# PROB_S7CAS_FPGA_2.net
KiCad netlist of a schematic drawn in Altium Designer
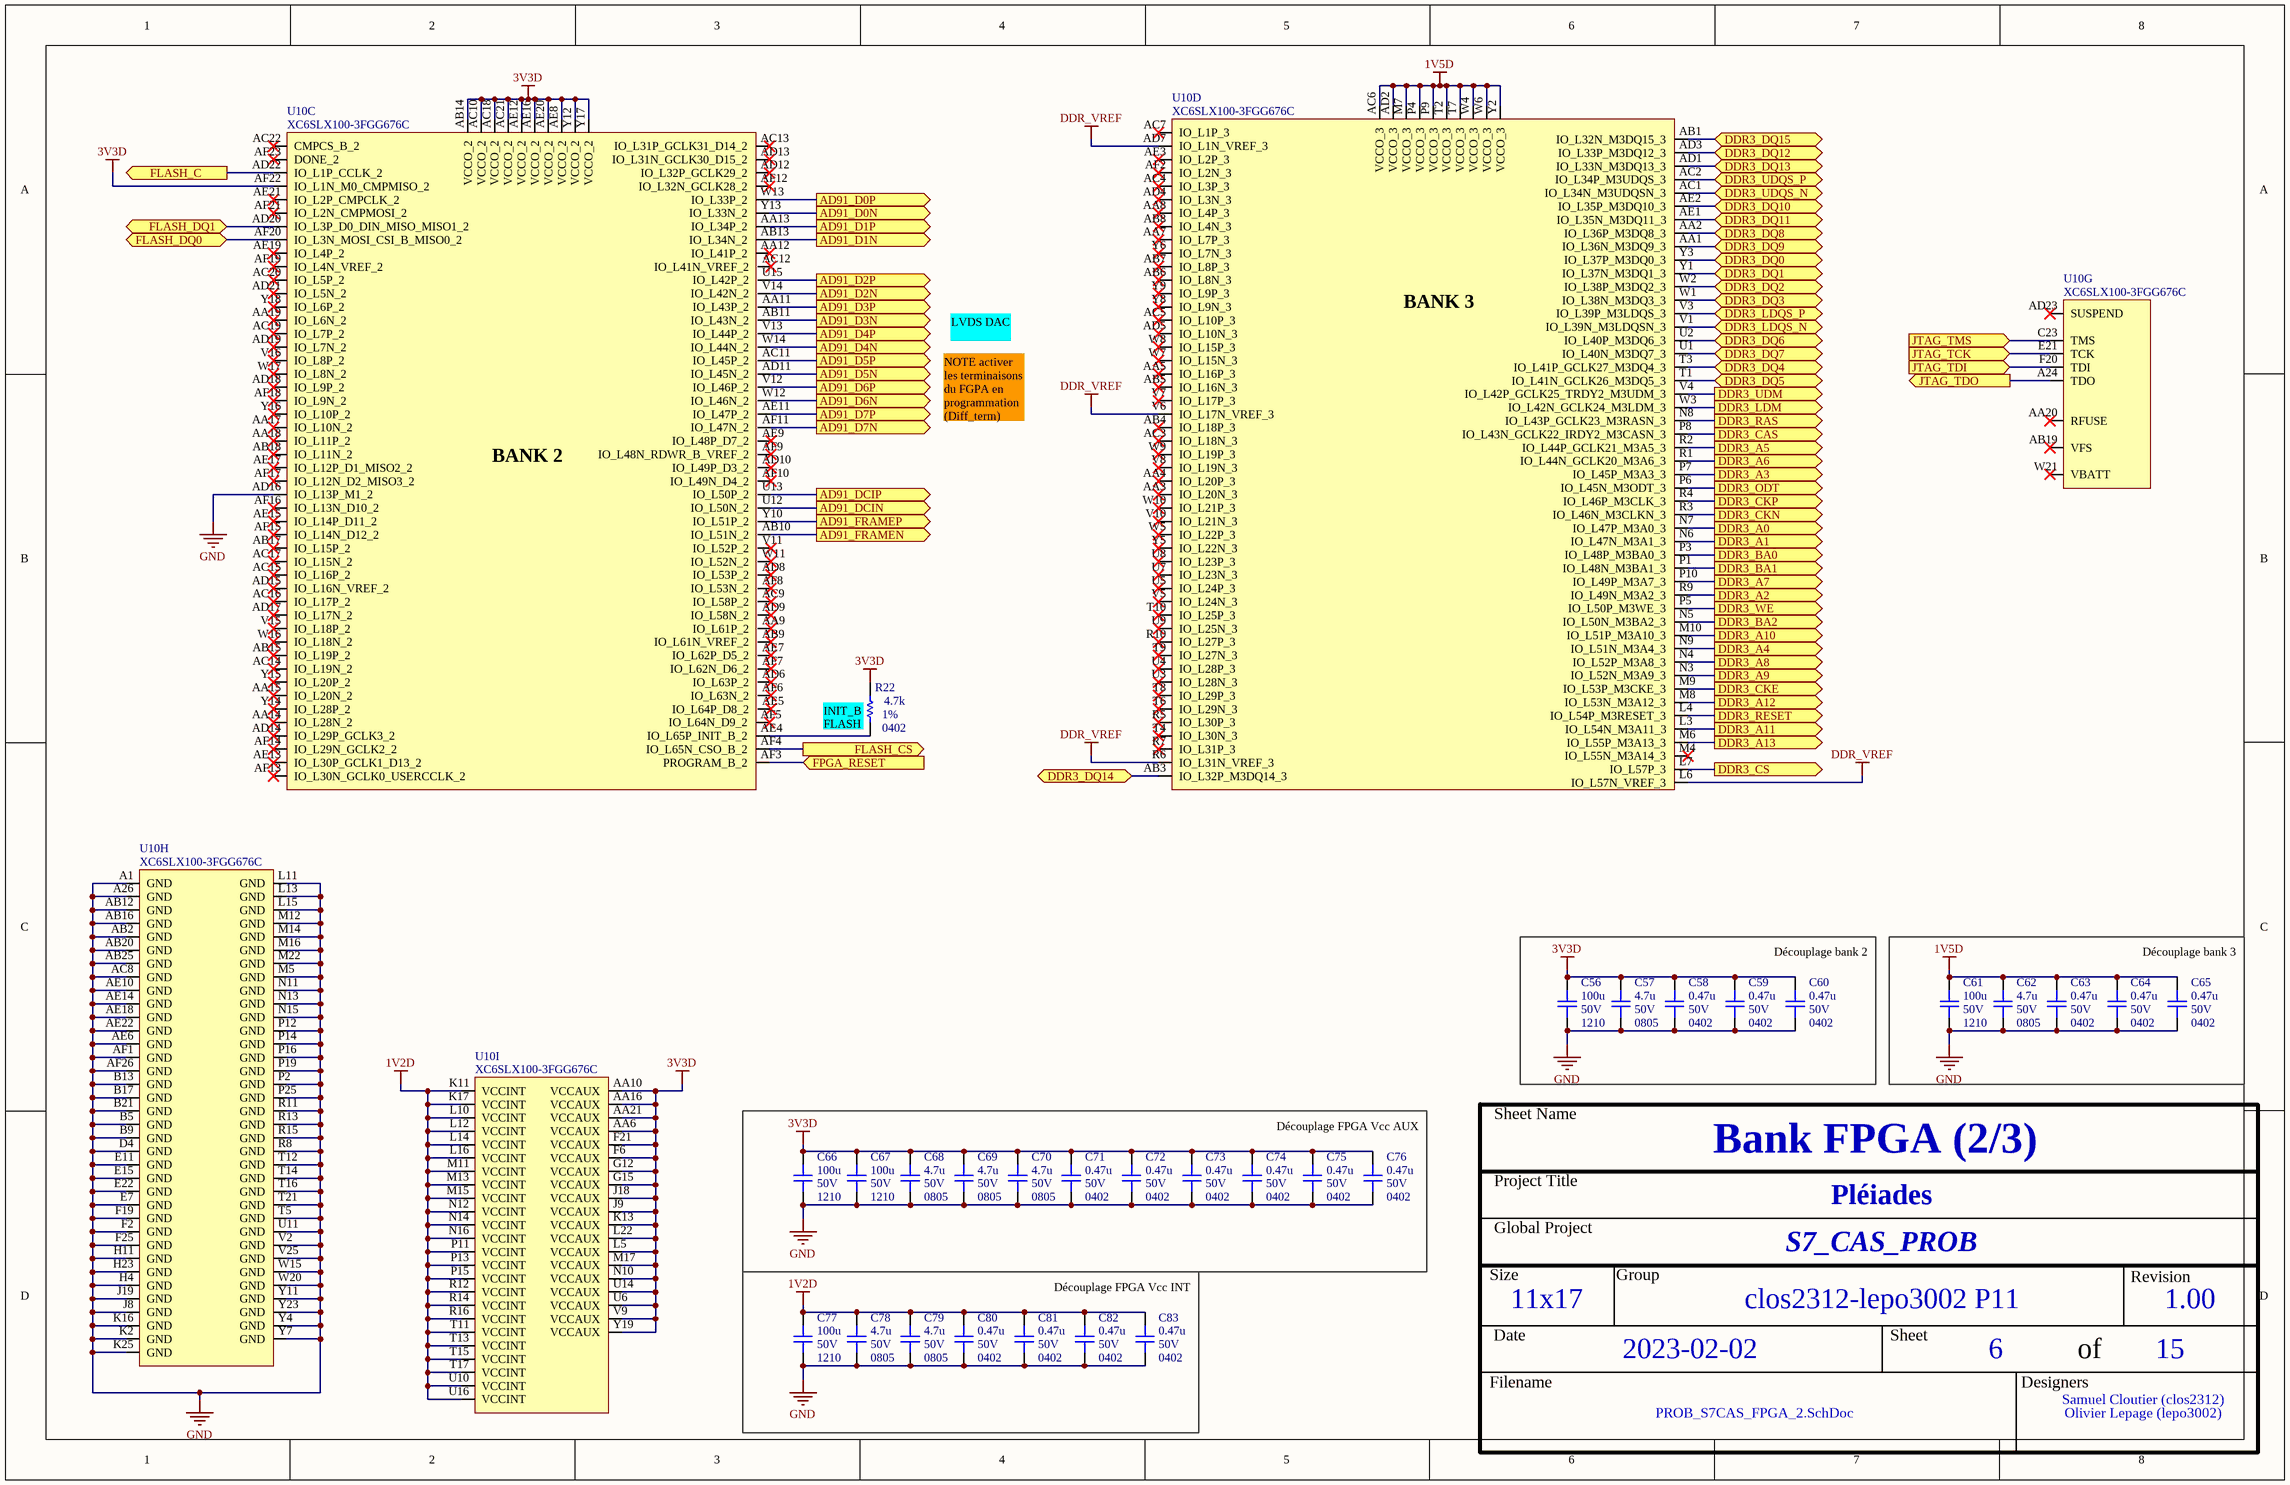
[diagram p0: PROB_S7CAS_FPGA_2.SchDoc]

(export (version "E")
  (design (tool "Eeschema 10.0.6"))
  (components
    (comp (ref "C56")
      (value "100u")
      (footprint "CAP_1210")
      (description "CAP - 1210")
      (fields
        (field (name "VOLTAGE") "50V")
        (field (name "PACKAGE") "1210")
        (field (name "CREATEDBY") "Jonathan Bouchard")
      )
      (libsource (lib "S7CAS_LIB2021") (part "CAP - 1210"))
    )
    (comp (ref "C57")
      (value "4.7u")
      (footprint "CAP_0805")
      (description "CAP - 0805")
      (fields
        (field (name "VOLTAGE") "50V")
        (field (name "PACKAGE") "0805")
        (field (name "CREATEDBY") "Jonathan Bouchard")
      )
      (libsource (lib "S7CAS_LIB2021") (part "CAP - 0805"))
    )
    (comp (ref "C58")
      (value "0.47u")
      (footprint "CAP_0402")
      (description "CAP - 0402")
      (fields
        (field (name "VOLTAGE") "50V")
        (field (name "PACKAGE") "0402")
        (field (name "CREATEDBY") "Jonathan Bouchard")
      )
      (libsource (lib "S7CAS_LIB2021") (part "CAP - 0402"))
    )
    (comp (ref "C59")
      (value "0.47u")
      (footprint "CAP_0402")
      (description "CAP - 0402")
      (fields
        (field (name "VOLTAGE") "50V")
        (field (name "PACKAGE") "0402")
        (field (name "CREATEDBY") "Jonathan Bouchard")
      )
      (libsource (lib "S7CAS_LIB2021") (part "CAP - 0402"))
    )
    (comp (ref "C60")
      (value "0.47u")
      (footprint "CAP_0402")
      (description "CAP - 0402")
      (fields
        (field (name "VOLTAGE") "50V")
        (field (name "PACKAGE") "0402")
        (field (name "CREATEDBY") "Jonathan Bouchard")
      )
      (libsource (lib "S7CAS_LIB2021") (part "CAP - 0402"))
    )
    (comp (ref "C61")
      (value "100u")
      (footprint "CAP_1210")
      (description "CAP - 1210")
      (fields
        (field (name "VOLTAGE") "50V")
        (field (name "PACKAGE") "1210")
        (field (name "CREATEDBY") "Jonathan Bouchard")
      )
      (libsource (lib "S7CAS_LIB2021") (part "CAP - 1210"))
    )
    (comp (ref "C62")
      (value "4.7u")
      (footprint "CAP_0805")
      (description "CAP - 0805")
      (fields
        (field (name "VOLTAGE") "50V")
        (field (name "PACKAGE") "0805")
        (field (name "CREATEDBY") "Jonathan Bouchard")
      )
      (libsource (lib "S7CAS_LIB2021") (part "CAP - 0805"))
    )
    (comp (ref "C63")
      (value "0.47u")
      (footprint "CAP_0402")
      (description "CAP - 0402")
      (fields
        (field (name "VOLTAGE") "50V")
        (field (name "PACKAGE") "0402")
        (field (name "CREATEDBY") "Jonathan Bouchard")
      )
      (libsource (lib "S7CAS_LIB2021") (part "CAP - 0402"))
    )
    (comp (ref "C64")
      (value "0.47u")
      (footprint "CAP_0402")
      (description "CAP - 0402")
      (fields
        (field (name "VOLTAGE") "50V")
        (field (name "PACKAGE") "0402")
        (field (name "CREATEDBY") "Jonathan Bouchard")
      )
      (libsource (lib "S7CAS_LIB2021") (part "CAP - 0402"))
    )
    (comp (ref "C65")
      (value "0.47u")
      (footprint "CAP_0402")
      (description "CAP - 0402")
      (fields
        (field (name "VOLTAGE") "50V")
        (field (name "PACKAGE") "0402")
        (field (name "CREATEDBY") "Jonathan Bouchard")
      )
      (libsource (lib "S7CAS_LIB2021") (part "CAP - 0402"))
    )
    (comp (ref "C66")
      (value "100u")
      (footprint "CAP_1210")
      (description "CAP - 1210")
      (fields
        (field (name "VOLTAGE") "50V")
        (field (name "PACKAGE") "1210")
        (field (name "CREATEDBY") "Jonathan Bouchard")
      )
      (libsource (lib "S7CAS_LIB2021") (part "CAP - 1210"))
    )
    (comp (ref "C67")
      (value "100u")
      (footprint "CAP_1210")
      (description "CAP - 1210")
      (fields
        (field (name "VOLTAGE") "50V")
        (field (name "PACKAGE") "1210")
        (field (name "CREATEDBY") "Jonathan Bouchard")
      )
      (libsource (lib "S7CAS_LIB2021") (part "CAP - 1210"))
    )
    (comp (ref "C68")
      (value "4.7u")
      (footprint "CAP_0805")
      (description "CAP - 0805")
      (fields
        (field (name "VOLTAGE") "50V")
        (field (name "PACKAGE") "0805")
        (field (name "CREATEDBY") "Jonathan Bouchard")
      )
      (libsource (lib "S7CAS_LIB2021") (part "CAP - 0805"))
    )
    (comp (ref "C69")
      (value "4.7u")
      (footprint "CAP_0805")
      (description "CAP - 0805")
      (fields
        (field (name "VOLTAGE") "50V")
        (field (name "PACKAGE") "0805")
        (field (name "CREATEDBY") "Jonathan Bouchard")
      )
      (libsource (lib "S7CAS_LIB2021") (part "CAP - 0805"))
    )
    (comp (ref "C70")
      (value "4.7u")
      (footprint "CAP_0805")
      (description "CAP - 0805")
      (fields
        (field (name "VOLTAGE") "50V")
        (field (name "PACKAGE") "0805")
        (field (name "CREATEDBY") "Jonathan Bouchard")
      )
      (libsource (lib "S7CAS_LIB2021") (part "CAP - 0805"))
    )
    (comp (ref "C71")
      (value "0.47u")
      (footprint "CAP_0402")
      (description "CAP - 0402")
      (fields
        (field (name "VOLTAGE") "50V")
        (field (name "PACKAGE") "0402")
        (field (name "CREATEDBY") "Jonathan Bouchard")
      )
      (libsource (lib "S7CAS_LIB2021") (part "CAP - 0402"))
    )
    (comp (ref "C72")
      (value "0.47u")
      (footprint "CAP_0402")
      (description "CAP - 0402")
      (fields
        (field (name "VOLTAGE") "50V")
        (field (name "PACKAGE") "0402")
        (field (name "CREATEDBY") "Jonathan Bouchard")
      )
      (libsource (lib "S7CAS_LIB2021") (part "CAP - 0402"))
    )
    (comp (ref "C73")
      (value "0.47u")
      (footprint "CAP_0402")
      (description "CAP - 0402")
      (fields
        (field (name "VOLTAGE") "50V")
        (field (name "PACKAGE") "0402")
        (field (name "CREATEDBY") "Jonathan Bouchard")
      )
      (libsource (lib "S7CAS_LIB2021") (part "CAP - 0402"))
    )
    (comp (ref "C74")
      (value "0.47u")
      (footprint "CAP_0402")
      (description "CAP - 0402")
      (fields
        (field (name "VOLTAGE") "50V")
        (field (name "PACKAGE") "0402")
        (field (name "CREATEDBY") "Jonathan Bouchard")
      )
      (libsource (lib "S7CAS_LIB2021") (part "CAP - 0402"))
    )
    (comp (ref "C75")
      (value "0.47u")
      (footprint "CAP_0402")
      (description "CAP - 0402")
      (fields
        (field (name "VOLTAGE") "50V")
        (field (name "PACKAGE") "0402")
        (field (name "CREATEDBY") "Jonathan Bouchard")
      )
      (libsource (lib "S7CAS_LIB2021") (part "CAP - 0402"))
    )
    (comp (ref "C76")
      (value "0.47u")
      (footprint "CAP_0402")
      (description "CAP - 0402")
      (fields
        (field (name "VOLTAGE") "50V")
        (field (name "PACKAGE") "0402")
        (field (name "CREATEDBY") "Jonathan Bouchard")
      )
      (libsource (lib "S7CAS_LIB2021") (part "CAP - 0402"))
    )
    (comp (ref "C77")
      (value "100u")
      (footprint "CAP_1210")
      (description "CAP - 1210")
      (fields
        (field (name "VOLTAGE") "50V")
        (field (name "PACKAGE") "1210")
        (field (name "CREATEDBY") "Jonathan Bouchard")
      )
      (libsource (lib "S7CAS_LIB2021") (part "CAP - 1210"))
    )
    (comp (ref "C78")
      (value "4.7u")
      (footprint "CAP_0805")
      (description "CAP - 0805")
      (fields
        (field (name "VOLTAGE") "50V")
        (field (name "PACKAGE") "0805")
        (field (name "CREATEDBY") "Jonathan Bouchard")
      )
      (libsource (lib "S7CAS_LIB2021") (part "CAP - 0805"))
    )
    (comp (ref "C79")
      (value "4.7u")
      (footprint "CAP_0805")
      (description "CAP - 0805")
      (fields
        (field (name "VOLTAGE") "50V")
        (field (name "PACKAGE") "0805")
        (field (name "CREATEDBY") "Jonathan Bouchard")
      )
      (libsource (lib "S7CAS_LIB2021") (part "CAP - 0805"))
    )
    (comp (ref "C80")
      (value "0.47u")
      (footprint "CAP_0402")
      (description "CAP - 0402")
      (fields
        (field (name "VOLTAGE") "50V")
        (field (name "PACKAGE") "0402")
        (field (name "CREATEDBY") "Jonathan Bouchard")
      )
      (libsource (lib "S7CAS_LIB2021") (part "CAP - 0402"))
    )
    (comp (ref "C81")
      (value "0.47u")
      (footprint "CAP_0402")
      (description "CAP - 0402")
      (fields
        (field (name "VOLTAGE") "50V")
        (field (name "PACKAGE") "0402")
        (field (name "CREATEDBY") "Jonathan Bouchard")
      )
      (libsource (lib "S7CAS_LIB2021") (part "CAP - 0402"))
    )
    (comp (ref "C82")
      (value "0.47u")
      (footprint "CAP_0402")
      (description "CAP - 0402")
      (fields
        (field (name "VOLTAGE") "50V")
        (field (name "PACKAGE") "0402")
        (field (name "CREATEDBY") "Jonathan Bouchard")
      )
      (libsource (lib "S7CAS_LIB2021") (part "CAP - 0402"))
    )
    (comp (ref "C83")
      (value "0.47u")
      (footprint "CAP_0402")
      (description "CAP - 0402")
      (fields
        (field (name "VOLTAGE") "50V")
        (field (name "PACKAGE") "0402")
        (field (name "CREATEDBY") "Jonathan Bouchard")
      )
      (libsource (lib "S7CAS_LIB2021") (part "CAP - 0402"))
    )
    (comp (ref "R22")
      (value "4.7k")
      (footprint "RES_0402")
      (description "RES - 0402")
      (fields
        (field (name "VOLTAGE") "50V")
        (field (name "POWER") "1/16W")
        (field (name "PACKAGE") "0402")
        (field (name "PRECISION") "1%")
        (field (name "CREATEDBY") "Jonathan Bouchard")
      )
      (libsource (lib "S7CAS_LIB2021") (part "RES - 0402"))
    )
    (comp (ref "U10")
      (value "XC6SLX100-3FGG676C")
      (footprint "FPGA_XILINX_FGG676")
      (description "FPGA - XILINX SPARTAN 6 480 I/O - BGA-676")
      (fields
        (field (name "VOLTAGE") "1.14 V ~ 1.26 V")
        (field (name "MFG") "Xilinx")
        (field (name "CREATEDBY") "Jonathan Bouchard")
      )
      (libsource (lib "S7CAS_LIB2021") (part "FPGA_XC6SLX100-3FGG676C"))
    )
  )
  (nets
    (net (code "1") (name "/AD91_D0N") (class "Default")
      (node (ref "U10") (pin "Y13") (pinfunction "IO_L33N_2_Y13") (pintype "passive"))
    )
    (net (code "2") (name "/AD91_D0P") (class "Default")
      (node (ref "U10") (pin "W13") (pinfunction "IO_L33P_2_W13") (pintype "passive"))
    )
    (net (code "3") (name "/AD91_D1N") (class "Default")
      (node (ref "U10") (pin "AB13") (pinfunction "IO_L34N_2_AB13") (pintype "passive"))
    )
    (net (code "4") (name "/AD91_D1P") (class "Default")
      (node (ref "U10") (pin "AA13") (pinfunction "IO_L34P_2_AA13") (pintype "passive"))
    )
    (net (code "5") (name "/AD91_D2N") (class "Default")
      (node (ref "U10") (pin "V14") (pinfunction "IO_L42N_2_V14") (pintype "passive"))
    )
    (net (code "6") (name "/AD91_D2P") (class "Default")
      (node (ref "U10") (pin "U15") (pinfunction "IO_L42P_2_U15") (pintype "passive"))
    )
    (net (code "7") (name "/AD91_D3N") (class "Default")
      (node (ref "U10") (pin "AB11") (pinfunction "IO_L43N_2_AB11") (pintype "passive"))
    )
    (net (code "8") (name "/AD91_D3P") (class "Default")
      (node (ref "U10") (pin "AA11") (pinfunction "IO_L43P_2_AA11") (pintype "passive"))
    )
    (net (code "9") (name "/AD91_D4N") (class "Default")
      (node (ref "U10") (pin "W14") (pinfunction "IO_L44N_2_W14") (pintype "passive"))
    )
    (net (code "10") (name "/AD91_D4P") (class "Default")
      (node (ref "U10") (pin "V13") (pinfunction "IO_L44P_2_V13") (pintype "passive"))
    )
    (net (code "11") (name "/AD91_D5N") (class "Default")
      (node (ref "U10") (pin "AD11") (pinfunction "IO_L45N_2_AD11") (pintype "passive"))
    )
    (net (code "12") (name "/AD91_D5P") (class "Default")
      (node (ref "U10") (pin "AC11") (pinfunction "IO_L45P_2_AC11") (pintype "passive"))
    )
    (net (code "13") (name "/AD91_D6N") (class "Default")
      (node (ref "U10") (pin "W12") (pinfunction "IO_L46N_2_W12") (pintype "passive"))
    )
    (net (code "14") (name "/AD91_D6P") (class "Default")
      (node (ref "U10") (pin "V12") (pinfunction "IO_L46P_2_V12") (pintype "passive"))
    )
    (net (code "15") (name "/AD91_D7N") (class "Default")
      (node (ref "U10") (pin "AF11") (pinfunction "IO_L47N_2_AF11") (pintype "passive"))
    )
    (net (code "16") (name "/AD91_D7P") (class "Default")
      (node (ref "U10") (pin "AE11") (pinfunction "IO_L47P_2_AE11") (pintype "passive"))
    )
    (net (code "17") (name "/AD91_DCIN") (class "Default")
      (node (ref "U10") (pin "U12") (pinfunction "IO_L50N_2_U12") (pintype "passive"))
    )
    (net (code "18") (name "/AD91_DCIP") (class "Default")
      (node (ref "U10") (pin "U13") (pinfunction "IO_L50P_2_U13") (pintype "passive"))
    )
    (net (code "19") (name "/AD91_FRAMEN") (class "Default")
      (node (ref "U10") (pin "AB10") (pinfunction "IO_L51N_2_AB10") (pintype "passive"))
    )
    (net (code "20") (name "/AD91_FRAMEP") (class "Default")
      (node (ref "U10") (pin "Y10") (pinfunction "IO_L51P_2_Y10") (pintype "passive"))
    )
    (net (code "21") (name "/DDR3_A0") (class "Default")
      (node (ref "U10") (pin "N7") (pinfunction "IO_L47P_M3A0_3_N7") (pintype "passive"))
    )
    (net (code "22") (name "/DDR3_A1") (class "Default")
      (node (ref "U10") (pin "N6") (pinfunction "IO_L47N_M3A1_3_N6") (pintype "passive"))
    )
    (net (code "23") (name "/DDR3_A2") (class "Default")
      (node (ref "U10") (pin "R9") (pinfunction "IO_L49N_M3A2_3_R9") (pintype "passive"))
    )
    (net (code "24") (name "/DDR3_A3") (class "Default")
      (node (ref "U10") (pin "P7") (pinfunction "IO_L45P_M3A3_3_P7") (pintype "passive"))
    )
    (net (code "25") (name "/DDR3_A4") (class "Default")
      (node (ref "U10") (pin "N9") (pinfunction "IO_L51N_M3A4_3_N9") (pintype "passive"))
    )
    (net (code "26") (name "/DDR3_A5") (class "Default")
      (node (ref "U10") (pin "R2") (pinfunction "IO_L44P_GCLK21_M3A5_3_R2") (pintype "passive"))
    )
    (net (code "27") (name "/DDR3_A6") (class "Default")
      (node (ref "U10") (pin "R1") (pinfunction "IO_L44N_GCLK20_M3A6_3_R1") (pintype "passive"))
    )
    (net (code "28") (name "/DDR3_A7") (class "Default")
      (node (ref "U10") (pin "P10") (pinfunction "IO_L49P_M3A7_3_P10") (pintype "passive"))
    )
    (net (code "29") (name "/DDR3_A8") (class "Default")
      (node (ref "U10") (pin "N4") (pinfunction "IO_L52P_M3A8_3_N4") (pintype "passive"))
    )
    (net (code "30") (name "/DDR3_A9") (class "Default")
      (node (ref "U10") (pin "N3") (pinfunction "IO_L52N_M3A9_3_N3") (pintype "passive"))
    )
    (net (code "31") (name "/DDR3_A10") (class "Default")
      (node (ref "U10") (pin "M10") (pinfunction "IO_L51P_M3A10_3_M10") (pintype "passive"))
    )
    (net (code "32") (name "/DDR3_A11") (class "Default")
      (node (ref "U10") (pin "L3") (pinfunction "IO_L54N_M3A11_3_L3") (pintype "passive"))
    )
    (net (code "33") (name "/DDR3_A12") (class "Default")
      (node (ref "U10") (pin "M8") (pinfunction "IO_L53N_M3A12_3_M8") (pintype "passive"))
    )
    (net (code "34") (name "/DDR3_A13") (class "Default")
      (node (ref "U10") (pin "M6") (pinfunction "IO_L55P_M3A13_3_M6") (pintype "passive"))
    )
    (net (code "35") (name "/DDR3_BA0") (class "Default")
      (node (ref "U10") (pin "P3") (pinfunction "IO_L48P_M3BA0_3_P3") (pintype "passive"))
    )
    (net (code "36") (name "/DDR3_BA1") (class "Default")
      (node (ref "U10") (pin "P1") (pinfunction "IO_L48N_M3BA1_3_P1") (pintype "passive"))
    )
    (net (code "37") (name "/DDR3_BA2") (class "Default")
      (node (ref "U10") (pin "N5") (pinfunction "IO_L50N_M3BA2_3_N5") (pintype "passive"))
    )
    (net (code "38") (name "/DDR3_CAS") (class "Default")
      (node (ref "U10") (pin "P8") (pinfunction "IO_L43N_GCLK22_IRDY2_M3CASN_3_P8") (pintype "passive"))
    )
    (net (code "39") (name "/DDR3_CKE") (class "Default")
      (node (ref "U10") (pin "M9") (pinfunction "IO_L53P_M3CKE_3_M9") (pintype "passive"))
    )
    (net (code "40") (name "/DDR3_CKN") (class "Default")
      (node (ref "U10") (pin "R3") (pinfunction "IO_L46N_M3CLKN_3_R3") (pintype "passive"))
    )
    (net (code "41") (name "/DDR3_CKP") (class "Default")
      (node (ref "U10") (pin "R4") (pinfunction "IO_L46P_M3CLK_3_R4") (pintype "passive"))
    )
    (net (code "42") (name "/DDR3_CS") (class "Default")
      (node (ref "U10") (pin "L7") (pinfunction "IO_L57P_3_L7") (pintype "passive"))
    )
    (net (code "43") (name "/DDR3_DQ0") (class "Default")
      (node (ref "U10") (pin "Y3") (pinfunction "IO_L37P_M3DQ0_3_Y3") (pintype "passive"))
    )
    (net (code "44") (name "/DDR3_DQ1") (class "Default")
      (node (ref "U10") (pin "Y1") (pinfunction "IO_L37N_M3DQ1_3_Y1") (pintype "passive"))
    )
    (net (code "45") (name "/DDR3_DQ2") (class "Default")
      (node (ref "U10") (pin "W2") (pinfunction "IO_L38P_M3DQ2_3_W2") (pintype "passive"))
    )
    (net (code "46") (name "/DDR3_DQ3") (class "Default")
      (node (ref "U10") (pin "W1") (pinfunction "IO_L38N_M3DQ3_3_W1") (pintype "passive"))
    )
    (net (code "47") (name "/DDR3_DQ4") (class "Default")
      (node (ref "U10") (pin "T3") (pinfunction "IO_L41P_GCLK27_M3DQ4_3_T3") (pintype "passive"))
    )
    (net (code "48") (name "/DDR3_DQ5") (class "Default")
      (node (ref "U10") (pin "T1") (pinfunction "IO_L41N_GCLK26_M3DQ5_3_T1") (pintype "passive"))
    )
    (net (code "49") (name "/DDR3_DQ6") (class "Default")
      (node (ref "U10") (pin "U2") (pinfunction "IO_L40P_M3DQ6_3_U2") (pintype "passive"))
    )
    (net (code "50") (name "/DDR3_DQ7") (class "Default")
      (node (ref "U10") (pin "U1") (pinfunction "IO_L40N_M3DQ7_3_U1") (pintype "passive"))
    )
    (net (code "51") (name "/DDR3_DQ8") (class "Default")
      (node (ref "U10") (pin "AA2") (pinfunction "IO_L36P_M3DQ8_3_AA2") (pintype "passive"))
    )
    (net (code "52") (name "/DDR3_DQ9") (class "Default")
      (node (ref "U10") (pin "AA1") (pinfunction "IO_L36N_M3DQ9_3_AA1") (pintype "passive"))
    )
    (net (code "53") (name "/DDR3_DQ10") (class "Default")
      (node (ref "U10") (pin "AE2") (pinfunction "IO_L35P_M3DQ10_3_AE2") (pintype "passive"))
    )
    (net (code "54") (name "/DDR3_DQ11") (class "Default")
      (node (ref "U10") (pin "AE1") (pinfunction "IO_L35N_M3DQ11_3_AE1") (pintype "passive"))
    )
    (net (code "55") (name "/DDR3_DQ12") (class "Default")
      (node (ref "U10") (pin "AD3") (pinfunction "IO_L33P_M3DQ12_3_AD3") (pintype "passive"))
    )
    (net (code "56") (name "/DDR3_DQ13") (class "Default")
      (node (ref "U10") (pin "AD1") (pinfunction "IO_L33N_M3DQ13_3_AD1") (pintype "passive"))
    )
    (net (code "57") (name "/DDR3_DQ14") (class "Default")
      (node (ref "U10") (pin "AB3") (pinfunction "IO_L32P_M3DQ14_3_AB3") (pintype "passive"))
    )
    (net (code "58") (name "/DDR3_DQ15") (class "Default")
      (node (ref "U10") (pin "AB1") (pinfunction "IO_L32N_M3DQ15_3_AB1") (pintype "passive"))
    )
    (net (code "59") (name "/DDR3_LDM") (class "Default")
      (node (ref "U10") (pin "W3") (pinfunction "IO_L42N_GCLK24_M3LDM_3_W3") (pintype "passive"))
    )
    (net (code "60") (name "/DDR3_LDQS_N") (class "Default")
      (node (ref "U10") (pin "V1") (pinfunction "IO_L39N_M3LDQSN_3_V1") (pintype "passive"))
    )
    (net (code "61") (name "/DDR3_LDQS_P") (class "Default")
      (node (ref "U10") (pin "V3") (pinfunction "IO_L39P_M3LDQS_3_V3") (pintype "passive"))
    )
    (net (code "62") (name "/DDR3_ODT") (class "Default")
      (node (ref "U10") (pin "P6") (pinfunction "IO_L45N_M3ODT_3_P6") (pintype "passive"))
    )
    (net (code "63") (name "/DDR3_RAS") (class "Default")
      (node (ref "U10") (pin "N8") (pinfunction "IO_L43P_GCLK23_M3RASN_3_N8") (pintype "passive"))
    )
    (net (code "64") (name "/DDR3_RESET") (class "Default")
      (node (ref "U10") (pin "L4") (pinfunction "IO_L54P_M3RESET_3_L4") (pintype "passive"))
    )
    (net (code "65") (name "/DDR3_UDM") (class "Default")
      (node (ref "U10") (pin "V4") (pinfunction "IO_L42P_GCLK25_TRDY2_M3UDM_3_V4") (pintype "passive"))
    )
    (net (code "66") (name "/DDR3_UDQS_N") (class "Default")
      (node (ref "U10") (pin "AC1") (pinfunction "IO_L34N_M3UDQSN_3_AC1") (pintype "passive"))
    )
    (net (code "67") (name "/DDR3_UDQS_P") (class "Default")
      (node (ref "U10") (pin "AC2") (pinfunction "IO_L34P_M3UDQS_3_AC2") (pintype "passive"))
    )
    (net (code "68") (name "/DDR3_WE") (class "Default")
      (node (ref "U10") (pin "P5") (pinfunction "IO_L50P_M3WE_3_P5") (pintype "passive"))
    )
    (net (code "69") (name "/FLASH_C") (class "Default")
      (node (ref "U10") (pin "AD22") (pinfunction "IO_L1P_CCLK_2_AD22") (pintype "passive"))
    )
    (net (code "70") (name "/FLASH_CS") (class "Default")
      (node (ref "U10") (pin "AF4") (pinfunction "IO_L65N_CSO_B_2_AF4") (pintype "passive"))
    )
    (net (code "71") (name "/FLASH_DQ0") (class "Default")
      (node (ref "U10") (pin "AF20") (pinfunction "IO_L3N_MOSI_CSI_B_MISO0_2_AF20") (pintype "passive"))
    )
    (net (code "72") (name "/FLASH_DQ1") (class "Default")
      (node (ref "U10") (pin "AD20") (pinfunction "IO_L3P_D0_DIN_MISO_MISO1_2_AD20") (pintype "passive"))
    )
    (net (code "73") (name "/FPGA_RESET") (class "Default")
      (node (ref "U10") (pin "AF3") (pinfunction "PROGRAM_B_2_AF3") (pintype "passive"))
    )
    (net (code "74") (name "/JTAG_TCK") (class "Default")
      (node (ref "U10") (pin "E21") (pinfunction "TCK_E21") (pintype "passive"))
    )
    (net (code "75") (name "/JTAG_TDI") (class "Default")
      (node (ref "U10") (pin "F20") (pinfunction "TDI_F20") (pintype "passive"))
    )
    (net (code "76") (name "/JTAG_TDO") (class "Default")
      (node (ref "U10") (pin "A24") (pinfunction "TDO_A24") (pintype "passive"))
    )
    (net (code "77") (name "/JTAG_TMS") (class "Default")
      (node (ref "U10") (pin "C23") (pinfunction "TMS_C23") (pintype "passive"))
    )
    (net (code "78") (name "1V2D") (class "Default")
      (node (ref "C77") (pin "2") (pinfunction "2_2") (pintype "passive"))
      (node (ref "C78") (pin "2") (pinfunction "2_2") (pintype "passive"))
      (node (ref "C79") (pin "2") (pinfunction "2_2") (pintype "passive"))
      (node (ref "C80") (pin "2") (pinfunction "2_2") (pintype "passive"))
      (node (ref "C81") (pin "2") (pinfunction "2_2") (pintype "passive"))
      (node (ref "C82") (pin "2") (pinfunction "2_2") (pintype "passive"))
      (node (ref "C83") (pin "2") (pinfunction "2_2") (pintype "passive"))
      (node (ref "U10") (pin "K11") (pinfunction "VCCINT_K11") (pintype "passive"))
      (node (ref "U10") (pin "K17") (pinfunction "VCCINT_K17") (pintype "passive"))
      (node (ref "U10") (pin "L10") (pinfunction "VCCINT_L10") (pintype "passive"))
      (node (ref "U10") (pin "L12") (pinfunction "VCCINT_L12") (pintype "passive"))
      (node (ref "U10") (pin "L14") (pinfunction "VCCINT_L14") (pintype "passive"))
      (node (ref "U10") (pin "L16") (pinfunction "VCCINT_L16") (pintype "passive"))
      (node (ref "U10") (pin "M11") (pinfunction "VCCINT_M11") (pintype "passive"))
      (node (ref "U10") (pin "M13") (pinfunction "VCCINT_M13") (pintype "passive"))
      (node (ref "U10") (pin "M15") (pinfunction "VCCINT_M15") (pintype "passive"))
      (node (ref "U10") (pin "N12") (pinfunction "VCCINT_N12") (pintype "passive"))
      (node (ref "U10") (pin "N14") (pinfunction "VCCINT_N14") (pintype "passive"))
      (node (ref "U10") (pin "N16") (pinfunction "VCCINT_N16") (pintype "passive"))
      (node (ref "U10") (pin "P11") (pinfunction "VCCINT_P11") (pintype "passive"))
      (node (ref "U10") (pin "P13") (pinfunction "VCCINT_P13") (pintype "passive"))
      (node (ref "U10") (pin "P15") (pinfunction "VCCINT_P15") (pintype "passive"))
      (node (ref "U10") (pin "R12") (pinfunction "VCCINT_R12") (pintype "passive"))
      (node (ref "U10") (pin "R14") (pinfunction "VCCINT_R14") (pintype "passive"))
      (node (ref "U10") (pin "R16") (pinfunction "VCCINT_R16") (pintype "passive"))
      (node (ref "U10") (pin "T11") (pinfunction "VCCINT_T11") (pintype "passive"))
      (node (ref "U10") (pin "T13") (pinfunction "VCCINT_T13") (pintype "passive"))
      (node (ref "U10") (pin "T15") (pinfunction "VCCINT_T15") (pintype "passive"))
      (node (ref "U10") (pin "T17") (pinfunction "VCCINT_T17") (pintype "passive"))
      (node (ref "U10") (pin "U10") (pinfunction "VCCINT_U10") (pintype "passive"))
      (node (ref "U10") (pin "U16") (pinfunction "VCCINT_U16") (pintype "passive"))
    )
    (net (code "79") (name "1V5D") (class "Default")
      (node (ref "C61") (pin "2") (pinfunction "2_2") (pintype "passive"))
      (node (ref "C62") (pin "2") (pinfunction "2_2") (pintype "passive"))
      (node (ref "C63") (pin "2") (pinfunction "2_2") (pintype "passive"))
      (node (ref "C64") (pin "2") (pinfunction "2_2") (pintype "passive"))
      (node (ref "C65") (pin "2") (pinfunction "2_2") (pintype "passive"))
      (node (ref "U10") (pin "AC6") (pinfunction "VCCO_3_AC6") (pintype "passive"))
      (node (ref "U10") (pin "AD2") (pinfunction "VCCO_3_AD2") (pintype "passive"))
      (node (ref "U10") (pin "M7") (pinfunction "VCCO_3_M7") (pintype "passive"))
      (node (ref "U10") (pin "P4") (pinfunction "VCCO_3_P4") (pintype "passive"))
      (node (ref "U10") (pin "P9") (pinfunction "VCCO_3_P9") (pintype "passive"))
      (node (ref "U10") (pin "T2") (pinfunction "VCCO_3_T2") (pintype "passive"))
      (node (ref "U10") (pin "T7") (pinfunction "VCCO_3_T7") (pintype "passive"))
      (node (ref "U10") (pin "W4") (pinfunction "VCCO_3_W4") (pintype "passive"))
      (node (ref "U10") (pin "W6") (pinfunction "VCCO_3_W6") (pintype "passive"))
      (node (ref "U10") (pin "Y2") (pinfunction "VCCO_3_Y2") (pintype "passive"))
    )
    (net (code "80") (name "3V3D") (class "Default")
      (node (ref "C56") (pin "2") (pinfunction "2_2") (pintype "passive"))
      (node (ref "C57") (pin "2") (pinfunction "2_2") (pintype "passive"))
      (node (ref "C58") (pin "2") (pinfunction "2_2") (pintype "passive"))
      (node (ref "C59") (pin "2") (pinfunction "2_2") (pintype "passive"))
      (node (ref "C60") (pin "2") (pinfunction "2_2") (pintype "passive"))
      (node (ref "C66") (pin "2") (pinfunction "2_2") (pintype "passive"))
      (node (ref "C67") (pin "2") (pinfunction "2_2") (pintype "passive"))
      (node (ref "C68") (pin "2") (pinfunction "2_2") (pintype "passive"))
      (node (ref "C69") (pin "2") (pinfunction "2_2") (pintype "passive"))
      (node (ref "C70") (pin "2") (pinfunction "2_2") (pintype "passive"))
      (node (ref "C71") (pin "2") (pinfunction "2_2") (pintype "passive"))
      (node (ref "C72") (pin "2") (pinfunction "2_2") (pintype "passive"))
      (node (ref "C73") (pin "2") (pinfunction "2_2") (pintype "passive"))
      (node (ref "C74") (pin "2") (pinfunction "2_2") (pintype "passive"))
      (node (ref "C75") (pin "2") (pinfunction "2_2") (pintype "passive"))
      (node (ref "C76") (pin "2") (pinfunction "2_2") (pintype "passive"))
      (node (ref "R22") (pin "2") (pinfunction "2_2") (pintype "passive"))
      (node (ref "U10") (pin "AA10") (pinfunction "VCCAUX_AA10") (pintype "passive"))
      (node (ref "U10") (pin "AA16") (pinfunction "VCCAUX_AA16") (pintype "passive"))
      (node (ref "U10") (pin "AA21") (pinfunction "VCCAUX_AA21") (pintype "passive"))
      (node (ref "U10") (pin "AA6") (pinfunction "VCCAUX_AA6") (pintype "passive"))
      (node (ref "U10") (pin "AB14") (pinfunction "VCCO_2_AB14") (pintype "passive"))
      (node (ref "U10") (pin "AC10") (pinfunction "VCCO_2_AC10") (pintype "passive"))
      (node (ref "U10") (pin "AC18") (pinfunction "VCCO_2_AC18") (pintype "passive"))
      (node (ref "U10") (pin "AC21") (pinfunction "VCCO_2_AC21") (pintype "passive"))
      (node (ref "U10") (pin "AE12") (pinfunction "VCCO_2_AE12") (pintype "passive"))
      (node (ref "U10") (pin "AE16") (pinfunction "VCCO_2_AE16") (pintype "passive"))
      (node (ref "U10") (pin "AE20") (pinfunction "VCCO_2_AE20") (pintype "passive"))
      (node (ref "U10") (pin "AE8") (pinfunction "VCCO_2_AE8") (pintype "passive"))
      (node (ref "U10") (pin "AF22") (pinfunction "IO_L1N_M0_CMPMISO_2_AF22") (pintype "passive"))
      (node (ref "U10") (pin "F21") (pinfunction "VCCAUX_F21") (pintype "passive"))
      (node (ref "U10") (pin "F6") (pinfunction "VCCAUX_F6") (pintype "passive"))
      (node (ref "U10") (pin "G12") (pinfunction "VCCAUX_G12") (pintype "passive"))
      (node (ref "U10") (pin "G15") (pinfunction "VCCAUX_G15") (pintype "passive"))
      (node (ref "U10") (pin "J18") (pinfunction "VCCAUX_J18") (pintype "passive"))
      (node (ref "U10") (pin "J9") (pinfunction "VCCAUX_J9") (pintype "passive"))
      (node (ref "U10") (pin "K13") (pinfunction "VCCAUX_K13") (pintype "passive"))
      (node (ref "U10") (pin "L22") (pinfunction "VCCAUX_L22") (pintype "passive"))
      (node (ref "U10") (pin "L5") (pinfunction "VCCAUX_L5") (pintype "passive"))
      (node (ref "U10") (pin "M17") (pinfunction "VCCAUX_M17") (pintype "passive"))
      (node (ref "U10") (pin "N10") (pinfunction "VCCAUX_N10") (pintype "passive"))
      (node (ref "U10") (pin "U14") (pinfunction "VCCAUX_U14") (pintype "passive"))
      (node (ref "U10") (pin "U6") (pinfunction "VCCAUX_U6") (pintype "passive"))
      (node (ref "U10") (pin "V9") (pinfunction "VCCAUX_V9") (pintype "passive"))
      (node (ref "U10") (pin "Y12") (pinfunction "VCCO_2_Y12") (pintype "passive"))
      (node (ref "U10") (pin "Y17") (pinfunction "VCCO_2_Y17") (pintype "passive"))
      (node (ref "U10") (pin "Y19") (pinfunction "VCCAUX_Y19") (pintype "passive"))
    )
    (net (code "81") (name "DDR_VREF") (class "Default")
      (node (ref "U10") (pin "AD7") (pinfunction "IO_L1N_VREF_3_AD7") (pintype "passive"))
      (node (ref "U10") (pin "L6") (pinfunction "IO_L57N_VREF_3_L6") (pintype "passive"))
      (node (ref "U10") (pin "R6") (pinfunction "IO_L31N_VREF_3_R6") (pintype "passive"))
      (node (ref "U10") (pin "V6") (pinfunction "IO_L17N_VREF_3_V6") (pintype "passive"))
    )
    (net (code "82") (name "GND") (class "Default")
      (node (ref "C56") (pin "1") (pinfunction "1_1") (pintype "passive"))
      (node (ref "C57") (pin "1") (pinfunction "1_1") (pintype "passive"))
      (node (ref "C58") (pin "1") (pinfunction "1_1") (pintype "passive"))
      (node (ref "C59") (pin "1") (pinfunction "1_1") (pintype "passive"))
      (node (ref "C60") (pin "1") (pinfunction "1_1") (pintype "passive"))
      (node (ref "C61") (pin "1") (pinfunction "1_1") (pintype "passive"))
      (node (ref "C62") (pin "1") (pinfunction "1_1") (pintype "passive"))
      (node (ref "C63") (pin "1") (pinfunction "1_1") (pintype "passive"))
      (node (ref "C64") (pin "1") (pinfunction "1_1") (pintype "passive"))
      (node (ref "C65") (pin "1") (pinfunction "1_1") (pintype "passive"))
      (node (ref "C66") (pin "1") (pinfunction "1_1") (pintype "passive"))
      (node (ref "C67") (pin "1") (pinfunction "1_1") (pintype "passive"))
      (node (ref "C68") (pin "1") (pinfunction "1_1") (pintype "passive"))
      (node (ref "C69") (pin "1") (pinfunction "1_1") (pintype "passive"))
      (node (ref "C70") (pin "1") (pinfunction "1_1") (pintype "passive"))
      (node (ref "C71") (pin "1") (pinfunction "1_1") (pintype "passive"))
      (node (ref "C72") (pin "1") (pinfunction "1_1") (pintype "passive"))
      (node (ref "C73") (pin "1") (pinfunction "1_1") (pintype "passive"))
      (node (ref "C74") (pin "1") (pinfunction "1_1") (pintype "passive"))
      (node (ref "C75") (pin "1") (pinfunction "1_1") (pintype "passive"))
      (node (ref "C76") (pin "1") (pinfunction "1_1") (pintype "passive"))
      (node (ref "C77") (pin "1") (pinfunction "1_1") (pintype "passive"))
      (node (ref "C78") (pin "1") (pinfunction "1_1") (pintype "passive"))
      (node (ref "C79") (pin "1") (pinfunction "1_1") (pintype "passive"))
      (node (ref "C80") (pin "1") (pinfunction "1_1") (pintype "passive"))
      (node (ref "C81") (pin "1") (pinfunction "1_1") (pintype "passive"))
      (node (ref "C82") (pin "1") (pinfunction "1_1") (pintype "passive"))
      (node (ref "C83") (pin "1") (pinfunction "1_1") (pintype "passive"))
      (node (ref "U10") (pin "A1") (pinfunction "GND_A1") (pintype "passive"))
      (node (ref "U10") (pin "A26") (pinfunction "GND_A26") (pintype "passive"))
      (node (ref "U10") (pin "AB12") (pinfunction "GND_AB12") (pintype "passive"))
      (node (ref "U10") (pin "AB16") (pinfunction "GND_AB16") (pintype "passive"))
      (node (ref "U10") (pin "AB2") (pinfunction "GND_AB2") (pintype "passive"))
      (node (ref "U10") (pin "AB20") (pinfunction "GND_AB20") (pintype "passive"))
      (node (ref "U10") (pin "AB25") (pinfunction "GND_AB25") (pintype "passive"))
      (node (ref "U10") (pin "AC8") (pinfunction "GND_AC8") (pintype "passive"))
      (node (ref "U10") (pin "AD16") (pinfunction "IO_L13P_M1_2_AD16") (pintype "passive"))
      (node (ref "U10") (pin "AE10") (pinfunction "GND_AE10") (pintype "passive"))
      (node (ref "U10") (pin "AE14") (pinfunction "GND_AE14") (pintype "passive"))
      (node (ref "U10") (pin "AE18") (pinfunction "GND_AE18") (pintype "passive"))
      (node (ref "U10") (pin "AE22") (pinfunction "GND_AE22") (pintype "passive"))
      (node (ref "U10") (pin "AE6") (pinfunction "GND_AE6") (pintype "passive"))
      (node (ref "U10") (pin "AF1") (pinfunction "GND_AF1") (pintype "passive"))
      (node (ref "U10") (pin "AF26") (pinfunction "GND_AF26") (pintype "passive"))
      (node (ref "U10") (pin "B13") (pinfunction "GND_B13") (pintype "passive"))
      (node (ref "U10") (pin "B17") (pinfunction "GND_B17") (pintype "passive"))
      (node (ref "U10") (pin "B21") (pinfunction "GND_B21") (pintype "passive"))
      (node (ref "U10") (pin "B5") (pinfunction "GND_B5") (pintype "passive"))
      (node (ref "U10") (pin "B9") (pinfunction "GND_B9") (pintype "passive"))
      (node (ref "U10") (pin "D4") (pinfunction "GND_D4") (pintype "passive"))
      (node (ref "U10") (pin "E11") (pinfunction "GND_E11") (pintype "passive"))
      (node (ref "U10") (pin "E15") (pinfunction "GND_E15") (pintype "passive"))
      (node (ref "U10") (pin "E22") (pinfunction "GND_E22") (pintype "passive"))
      (node (ref "U10") (pin "E7") (pinfunction "GND_E7") (pintype "passive"))
      (node (ref "U10") (pin "F19") (pinfunction "GND_F19") (pintype "passive"))
      (node (ref "U10") (pin "F2") (pinfunction "GND_F2") (pintype "passive"))
      (node (ref "U10") (pin "F25") (pinfunction "GND_F25") (pintype "passive"))
      (node (ref "U10") (pin "H11") (pinfunction "GND_H11") (pintype "passive"))
      (node (ref "U10") (pin "H23") (pinfunction "GND_H23") (pintype "passive"))
      (node (ref "U10") (pin "H4") (pinfunction "GND_H4") (pintype "passive"))
      (node (ref "U10") (pin "J19") (pinfunction "GND_J19") (pintype "passive"))
      (node (ref "U10") (pin "J8") (pinfunction "GND_J8") (pintype "passive"))
      (node (ref "U10") (pin "K16") (pinfunction "GND_K16") (pintype "passive"))
      (node (ref "U10") (pin "K2") (pinfunction "GND_K2") (pintype "passive"))
      (node (ref "U10") (pin "K25") (pinfunction "GND_K25") (pintype "passive"))
      (node (ref "U10") (pin "L11") (pinfunction "GND_L11") (pintype "passive"))
      (node (ref "U10") (pin "L13") (pinfunction "GND_L13") (pintype "passive"))
      (node (ref "U10") (pin "L15") (pinfunction "GND_L15") (pintype "passive"))
      (node (ref "U10") (pin "M12") (pinfunction "GND_M12") (pintype "passive"))
      (node (ref "U10") (pin "M14") (pinfunction "GND_M14") (pintype "passive"))
      (node (ref "U10") (pin "M16") (pinfunction "GND_M16") (pintype "passive"))
      (node (ref "U10") (pin "M22") (pinfunction "GND_M22") (pintype "passive"))
      (node (ref "U10") (pin "M5") (pinfunction "GND_M5") (pintype "passive"))
      (node (ref "U10") (pin "N11") (pinfunction "GND_N11") (pintype "passive"))
      (node (ref "U10") (pin "N13") (pinfunction "GND_N13") (pintype "passive"))
      (node (ref "U10") (pin "N15") (pinfunction "GND_N15") (pintype "passive"))
      (node (ref "U10") (pin "P12") (pinfunction "GND_P12") (pintype "passive"))
      (node (ref "U10") (pin "P14") (pinfunction "GND_P14") (pintype "passive"))
      (node (ref "U10") (pin "P16") (pinfunction "GND_P16") (pintype "passive"))
      (node (ref "U10") (pin "P19") (pinfunction "GND_P19") (pintype "passive"))
      (node (ref "U10") (pin "P2") (pinfunction "GND_P2") (pintype "passive"))
      (node (ref "U10") (pin "P25") (pinfunction "GND_P25") (pintype "passive"))
      (node (ref "U10") (pin "R11") (pinfunction "GND_R11") (pintype "passive"))
      (node (ref "U10") (pin "R13") (pinfunction "GND_R13") (pintype "passive"))
      (node (ref "U10") (pin "R15") (pinfunction "GND_R15") (pintype "passive"))
      (node (ref "U10") (pin "R8") (pinfunction "GND_R8") (pintype "passive"))
      (node (ref "U10") (pin "T12") (pinfunction "GND_T12") (pintype "passive"))
      (node (ref "U10") (pin "T14") (pinfunction "GND_T14") (pintype "passive"))
      (node (ref "U10") (pin "T16") (pinfunction "GND_T16") (pintype "passive"))
      (node (ref "U10") (pin "T21") (pinfunction "GND_T21") (pintype "passive"))
      (node (ref "U10") (pin "T5") (pinfunction "GND_T5") (pintype "passive"))
      (node (ref "U10") (pin "U11") (pinfunction "GND_U11") (pintype "passive"))
      (node (ref "U10") (pin "V2") (pinfunction "GND_V2") (pintype "passive"))
      (node (ref "U10") (pin "V25") (pinfunction "GND_V25") (pintype "passive"))
      (node (ref "U10") (pin "W15") (pinfunction "GND_W15") (pintype "passive"))
      (node (ref "U10") (pin "W20") (pinfunction "GND_W20") (pintype "passive"))
      (node (ref "U10") (pin "Y11") (pinfunction "GND_Y11") (pintype "passive"))
      (node (ref "U10") (pin "Y23") (pinfunction "GND_Y23") (pintype "passive"))
      (node (ref "U10") (pin "Y4") (pinfunction "GND_Y4") (pintype "passive"))
      (node (ref "U10") (pin "Y7") (pinfunction "GND_Y7") (pintype "passive"))
    )
    (net (code "83") (name "Net-(U10C-IO_L65P_INIT_B_2)") (class "Default")
      (node (ref "R22") (pin "1") (pinfunction "1_1") (pintype "passive"))
      (node (ref "U10") (pin "AE4") (pinfunction "IO_L65P_INIT_B_2_AE4") (pintype "passive"))
    )
    (net (code "84") (name "unconnected-(U10C-CMPCS_B_2-PadAC22)") (class "Default")
      (node (ref "U10") (pin "AC22") (pinfunction "CMPCS_B_2_AC22") (pintype "passive+no_connect"))
    )
    (net (code "85") (name "unconnected-(U10C-DONE_2-PadAF23)") (class "Default")
      (node (ref "U10") (pin "AF23") (pinfunction "DONE_2_AF23") (pintype "passive+no_connect"))
    )
    (net (code "86") (name "unconnected-(U10C-IO_L2N_CMPMOSI_2-PadAF21)") (class "Default")
      (node (ref "U10") (pin "AF21") (pinfunction "IO_L2N_CMPMOSI_2_AF21") (pintype "passive+no_connect"))
    )
    (net (code "87") (name "unconnected-(U10C-IO_L2P_CMPCLK_2-PadAE21)") (class "Default")
      (node (ref "U10") (pin "AE21") (pinfunction "IO_L2P_CMPCLK_2_AE21") (pintype "passive+no_connect"))
    )
    (net (code "88") (name "unconnected-(U10C-IO_L4N_VREF_2-PadAF19)") (class "Default")
      (node (ref "U10") (pin "AF19") (pinfunction "IO_L4N_VREF_2_AF19") (pintype "passive+no_connect"))
    )
    (net (code "89") (name "unconnected-(U10C-IO_L4P_2-PadAE19)") (class "Default")
      (node (ref "U10") (pin "AE19") (pinfunction "IO_L4P_2_AE19") (pintype "passive+no_connect"))
    )
    (net (code "90") (name "unconnected-(U10C-IO_L5N_2-PadAD21)") (class "Default")
      (node (ref "U10") (pin "AD21") (pinfunction "IO_L5N_2_AD21") (pintype "passive+no_connect"))
    )
    (net (code "91") (name "unconnected-(U10C-IO_L5P_2-PadAC20)") (class "Default")
      (node (ref "U10") (pin "AC20") (pinfunction "IO_L5P_2_AC20") (pintype "passive+no_connect"))
    )
    (net (code "92") (name "unconnected-(U10C-IO_L6N_2-PadAA19)") (class "Default")
      (node (ref "U10") (pin "AA19") (pinfunction "IO_L6N_2_AA19") (pintype "passive+no_connect"))
    )
    (net (code "93") (name "unconnected-(U10C-IO_L6P_2-PadY18)") (class "Default")
      (node (ref "U10") (pin "Y18") (pinfunction "IO_L6P_2_Y18") (pintype "passive+no_connect"))
    )
    (net (code "94") (name "unconnected-(U10C-IO_L7N_2-PadAD19)") (class "Default")
      (node (ref "U10") (pin "AD19") (pinfunction "IO_L7N_2_AD19") (pintype "passive+no_connect"))
    )
    (net (code "95") (name "unconnected-(U10C-IO_L7P_2-PadAC19)") (class "Default")
      (node (ref "U10") (pin "AC19") (pinfunction "IO_L7P_2_AC19") (pintype "passive+no_connect"))
    )
    (net (code "96") (name "unconnected-(U10C-IO_L8N_2-PadW17)") (class "Default")
      (node (ref "U10") (pin "W17") (pinfunction "IO_L8N_2_W17") (pintype "passive+no_connect"))
    )
    (net (code "97") (name "unconnected-(U10C-IO_L8P_2-PadV16)") (class "Default")
      (node (ref "U10") (pin "V16") (pinfunction "IO_L8P_2_V16") (pintype "passive+no_connect"))
    )
    (net (code "98") (name "unconnected-(U10C-IO_L9N_2-PadAF18)") (class "Default")
      (node (ref "U10") (pin "AF18") (pinfunction "IO_L9N_2_AF18") (pintype "passive+no_connect"))
    )
    (net (code "99") (name "unconnected-(U10C-IO_L9P_2-PadAD18)") (class "Default")
      (node (ref "U10") (pin "AD18") (pinfunction "IO_L9P_2_AD18") (pintype "passive+no_connect"))
    )
    (net (code "100") (name "unconnected-(U10C-IO_L10N_2-PadAA17)") (class "Default")
      (node (ref "U10") (pin "AA17") (pinfunction "IO_L10N_2_AA17") (pintype "passive+no_connect"))
    )
    (net (code "101") (name "unconnected-(U10C-IO_L10P_2-PadY16)") (class "Default")
      (node (ref "U10") (pin "Y16") (pinfunction "IO_L10P_2_Y16") (pintype "passive+no_connect"))
    )
    (net (code "102") (name "unconnected-(U10C-IO_L11N_2-PadAB18)") (class "Default")
      (node (ref "U10") (pin "AB18") (pinfunction "IO_L11N_2_AB18") (pintype "passive+no_connect"))
    )
    (net (code "103") (name "unconnected-(U10C-IO_L11P_2-PadAA18)") (class "Default")
      (node (ref "U10") (pin "AA18") (pinfunction "IO_L11P_2_AA18") (pintype "passive+no_connect"))
    )
    (net (code "104") (name "unconnected-(U10C-IO_L12N_D2_MISO3_2-PadAF17)") (class "Default")
      (node (ref "U10") (pin "AF17") (pinfunction "IO_L12N_D2_MISO3_2_AF17") (pintype "passive+no_connect"))
    )
    (net (code "105") (name "unconnected-(U10C-IO_L12P_D1_MISO2_2-PadAE17)") (class "Default")
      (node (ref "U10") (pin "AE17") (pinfunction "IO_L12P_D1_MISO2_2_AE17") (pintype "passive+no_connect"))
    )
    (net (code "106") (name "unconnected-(U10C-IO_L13N_D10_2-PadAF16)") (class "Default")
      (node (ref "U10") (pin "AF16") (pinfunction "IO_L13N_D10_2_AF16") (pintype "passive+no_connect"))
    )
    (net (code "107") (name "unconnected-(U10C-IO_L14N_D12_2-PadAF15)") (class "Default")
      (node (ref "U10") (pin "AF15") (pinfunction "IO_L14N_D12_2_AF15") (pintype "passive+no_connect"))
    )
    (net (code "108") (name "unconnected-(U10C-IO_L14P_D11_2-PadAE15)") (class "Default")
      (node (ref "U10") (pin "AE15") (pinfunction "IO_L14P_D11_2_AE15") (pintype "passive+no_connect"))
    )
    (net (code "109") (name "unconnected-(U10C-IO_L15N_2-PadAC17)") (class "Default")
      (node (ref "U10") (pin "AC17") (pinfunction "IO_L15N_2_AC17") (pintype "passive+no_connect"))
    )
    (net (code "110") (name "unconnected-(U10C-IO_L15P_2-PadAB17)") (class "Default")
      (node (ref "U10") (pin "AB17") (pinfunction "IO_L15P_2_AB17") (pintype "passive+no_connect"))
    )
    (net (code "111") (name "unconnected-(U10C-IO_L16N_VREF_2-PadAD15)") (class "Default")
      (node (ref "U10") (pin "AD15") (pinfunction "IO_L16N_VREF_2_AD15") (pintype "passive+no_connect"))
    )
    (net (code "112") (name "unconnected-(U10C-IO_L16P_2-PadAC15)") (class "Default")
      (node (ref "U10") (pin "AC15") (pinfunction "IO_L16P_2_AC15") (pintype "passive+no_connect"))
    )
    (net (code "113") (name "unconnected-(U10C-IO_L17N_2-PadAD17)") (class "Default")
      (node (ref "U10") (pin "AD17") (pinfunction "IO_L17N_2_AD17") (pintype "passive+no_connect"))
    )
    (net (code "114") (name "unconnected-(U10C-IO_L17P_2-PadAC16)") (class "Default")
      (node (ref "U10") (pin "AC16") (pinfunction "IO_L17P_2_AC16") (pintype "passive+no_connect"))
    )
    (net (code "115") (name "unconnected-(U10C-IO_L18N_2-PadW16)") (class "Default")
      (node (ref "U10") (pin "W16") (pinfunction "IO_L18N_2_W16") (pintype "passive+no_connect"))
    )
    (net (code "116") (name "unconnected-(U10C-IO_L18P_2-PadV15)") (class "Default")
      (node (ref "U10") (pin "V15") (pinfunction "IO_L18P_2_V15") (pintype "passive+no_connect"))
    )
    (net (code "117") (name "unconnected-(U10C-IO_L19N_2-PadAC14)") (class "Default")
      (node (ref "U10") (pin "AC14") (pinfunction "IO_L19N_2_AC14") (pintype "passive+no_connect"))
    )
    (net (code "118") (name "unconnected-(U10C-IO_L19P_2-PadAB15)") (class "Default")
      (node (ref "U10") (pin "AB15") (pinfunction "IO_L19P_2_AB15") (pintype "passive+no_connect"))
    )
    (net (code "119") (name "unconnected-(U10C-IO_L20N_2-PadAA15)") (class "Default")
      (node (ref "U10") (pin "AA15") (pinfunction "IO_L20N_2_AA15") (pintype "passive+no_connect"))
    )
    (net (code "120") (name "unconnected-(U10C-IO_L20P_2-PadY15)") (class "Default")
      (node (ref "U10") (pin "Y15") (pinfunction "IO_L20P_2_Y15") (pintype "passive+no_connect"))
    )
    (net (code "121") (name "unconnected-(U10C-IO_L28N_2-PadAA14)") (class "Default")
      (node (ref "U10") (pin "AA14") (pinfunction "IO_L28N_2_AA14") (pintype "passive+no_connect"))
    )
    (net (code "122") (name "unconnected-(U10C-IO_L28P_2-PadY14)") (class "Default")
      (node (ref "U10") (pin "Y14") (pinfunction "IO_L28P_2_Y14") (pintype "passive+no_connect"))
    )
    (net (code "123") (name "unconnected-(U10C-IO_L29N_GCLK2_2-PadAF14)") (class "Default")
      (node (ref "U10") (pin "AF14") (pinfunction "IO_L29N_GCLK2_2_AF14") (pintype "passive+no_connect"))
    )
    (net (code "124") (name "unconnected-(U10C-IO_L29P_GCLK3_2-PadAD14)") (class "Default")
      (node (ref "U10") (pin "AD14") (pinfunction "IO_L29P_GCLK3_2_AD14") (pintype "passive+no_connect"))
    )
    (net (code "125") (name "unconnected-(U10C-IO_L30N_GCLK0_USERCCLK_2-PadAF13)") (class "Default")
      (node (ref "U10") (pin "AF13") (pinfunction "IO_L30N_GCLK0_USERCCLK_2_AF13") (pintype "passive+no_connect"))
    )
    (net (code "126") (name "unconnected-(U10C-IO_L30P_GCLK1_D13_2-PadAE13)") (class "Default")
      (node (ref "U10") (pin "AE13") (pinfunction "IO_L30P_GCLK1_D13_2_AE13") (pintype "passive+no_connect"))
    )
    (net (code "127") (name "unconnected-(U10C-IO_L31N_GCLK30_D15_2-PadAD13)") (class "Default")
      (node (ref "U10") (pin "AD13") (pinfunction "IO_L31N_GCLK30_D15_2_AD13") (pintype "passive+no_connect"))
    )
    (net (code "128") (name "unconnected-(U10C-IO_L31P_GCLK31_D14_2-PadAC13)") (class "Default")
      (node (ref "U10") (pin "AC13") (pinfunction "IO_L31P_GCLK31_D14_2_AC13") (pintype "passive+no_connect"))
    )
    (net (code "129") (name "unconnected-(U10C-IO_L32N_GCLK28_2-PadAF12)") (class "Default")
      (node (ref "U10") (pin "AF12") (pinfunction "IO_L32N_GCLK28_2_AF12") (pintype "passive+no_connect"))
    )
    (net (code "130") (name "unconnected-(U10C-IO_L32P_GCLK29_2-PadAD12)") (class "Default")
      (node (ref "U10") (pin "AD12") (pinfunction "IO_L32P_GCLK29_2_AD12") (pintype "passive+no_connect"))
    )
    (net (code "131") (name "unconnected-(U10C-IO_L41N_VREF_2-PadAC12)") (class "Default")
      (node (ref "U10") (pin "AC12") (pinfunction "IO_L41N_VREF_2_AC12") (pintype "passive+no_connect"))
    )
    (net (code "132") (name "unconnected-(U10C-IO_L41P_2-PadAA12)") (class "Default")
      (node (ref "U10") (pin "AA12") (pinfunction "IO_L41P_2_AA12") (pintype "passive+no_connect"))
    )
    (net (code "133") (name "unconnected-(U10C-IO_L48N_RDWR_B_VREF_2-PadAF9)") (class "Default")
      (node (ref "U10") (pin "AF9") (pinfunction "IO_L48N_RDWR_B_VREF_2_AF9") (pintype "passive+no_connect"))
    )
    (net (code "134") (name "unconnected-(U10C-IO_L48P_D7_2-PadAE9)") (class "Default")
      (node (ref "U10") (pin "AE9") (pinfunction "IO_L48P_D7_2_AE9") (pintype "passive+no_connect"))
    )
    (net (code "135") (name "unconnected-(U10C-IO_L49N_D4_2-PadAF10)") (class "Default")
      (node (ref "U10") (pin "AF10") (pinfunction "IO_L49N_D4_2_AF10") (pintype "passive+no_connect"))
    )
    (net (code "136") (name "unconnected-(U10C-IO_L49P_D3_2-PadAD10)") (class "Default")
      (node (ref "U10") (pin "AD10") (pinfunction "IO_L49P_D3_2_AD10") (pintype "passive+no_connect"))
    )
    (net (code "137") (name "unconnected-(U10C-IO_L52N_2-PadW11)") (class "Default")
      (node (ref "U10") (pin "W11") (pinfunction "IO_L52N_2_W11") (pintype "passive+no_connect"))
    )
    (net (code "138") (name "unconnected-(U10C-IO_L52P_2-PadV11)") (class "Default")
      (node (ref "U10") (pin "V11") (pinfunction "IO_L52P_2_V11") (pintype "passive+no_connect"))
    )
    (net (code "139") (name "unconnected-(U10C-IO_L53N_2-PadAF8)") (class "Default")
      (node (ref "U10") (pin "AF8") (pinfunction "IO_L53N_2_AF8") (pintype "passive+no_connect"))
    )
    (net (code "140") (name "unconnected-(U10C-IO_L53P_2-PadAD8)") (class "Default")
      (node (ref "U10") (pin "AD8") (pinfunction "IO_L53P_2_AD8") (pintype "passive+no_connect"))
    )
    (net (code "141") (name "unconnected-(U10C-IO_L58N_2-PadAD9)") (class "Default")
      (node (ref "U10") (pin "AD9") (pinfunction "IO_L58N_2_AD9") (pintype "passive+no_connect"))
    )
    (net (code "142") (name "unconnected-(U10C-IO_L58P_2-PadAC9)") (class "Default")
      (node (ref "U10") (pin "AC9") (pinfunction "IO_L58P_2_AC9") (pintype "passive+no_connect"))
    )
    (net (code "143") (name "unconnected-(U10C-IO_L61N_VREF_2-PadAB9)") (class "Default")
      (node (ref "U10") (pin "AB9") (pinfunction "IO_L61N_VREF_2_AB9") (pintype "passive+no_connect"))
    )
    (net (code "144") (name "unconnected-(U10C-IO_L61P_2-PadAA9)") (class "Default")
      (node (ref "U10") (pin "AA9") (pinfunction "IO_L61P_2_AA9") (pintype "passive+no_connect"))
    )
    (net (code "145") (name "unconnected-(U10C-IO_L62N_D6_2-PadAF7)") (class "Default")
      (node (ref "U10") (pin "AF7") (pinfunction "IO_L62N_D6_2_AF7") (pintype "passive+no_connect"))
    )
    (net (code "146") (name "unconnected-(U10C-IO_L62P_D5_2-PadAE7)") (class "Default")
      (node (ref "U10") (pin "AE7") (pinfunction "IO_L62P_D5_2_AE7") (pintype "passive+no_connect"))
    )
    (net (code "147") (name "unconnected-(U10C-IO_L63N_2-PadAF6)") (class "Default")
      (node (ref "U10") (pin "AF6") (pinfunction "IO_L63N_2_AF6") (pintype "passive+no_connect"))
    )
    (net (code "148") (name "unconnected-(U10C-IO_L63P_2-PadAD6)") (class "Default")
      (node (ref "U10") (pin "AD6") (pinfunction "IO_L63P_2_AD6") (pintype "passive+no_connect"))
    )
    (net (code "149") (name "unconnected-(U10C-IO_L64N_D9_2-PadAF5)") (class "Default")
      (node (ref "U10") (pin "AF5") (pinfunction "IO_L64N_D9_2_AF5") (pintype "passive+no_connect"))
    )
    (net (code "150") (name "unconnected-(U10C-IO_L64P_D8_2-PadAE5)") (class "Default")
      (node (ref "U10") (pin "AE5") (pinfunction "IO_L64P_D8_2_AE5") (pintype "passive+no_connect"))
    )
    (net (code "151") (name "unconnected-(U10D-IO_L1P_3-PadAC7)") (class "Default")
      (node (ref "U10") (pin "AC7") (pinfunction "IO_L1P_3_AC7") (pintype "passive+no_connect"))
    )
    (net (code "152") (name "unconnected-(U10D-IO_L2N_3-PadAF2)") (class "Default")
      (node (ref "U10") (pin "AF2") (pinfunction "IO_L2N_3_AF2") (pintype "passive+no_connect"))
    )
    (net (code "153") (name "unconnected-(U10D-IO_L2P_3-PadAE3)") (class "Default")
      (node (ref "U10") (pin "AE3") (pinfunction "IO_L2P_3_AE3") (pintype "passive+no_connect"))
    )
    (net (code "154") (name "unconnected-(U10D-IO_L3N_3-PadAD4)") (class "Default")
      (node (ref "U10") (pin "AD4") (pinfunction "IO_L3N_3_AD4") (pintype "passive+no_connect"))
    )
    (net (code "155") (name "unconnected-(U10D-IO_L3P_3-PadAC4)") (class "Default")
      (node (ref "U10") (pin "AC4") (pinfunction "IO_L3P_3_AC4") (pintype "passive+no_connect"))
    )
    (net (code "156") (name "unconnected-(U10D-IO_L4N_3-PadAB8)") (class "Default")
      (node (ref "U10") (pin "AB8") (pinfunction "IO_L4N_3_AB8") (pintype "passive+no_connect"))
    )
    (net (code "157") (name "unconnected-(U10D-IO_L4P_3-PadAA8)") (class "Default")
      (node (ref "U10") (pin "AA8") (pinfunction "IO_L4P_3_AA8") (pintype "passive+no_connect"))
    )
    (net (code "158") (name "unconnected-(U10D-IO_L7N_3-PadY6)") (class "Default")
      (node (ref "U10") (pin "Y6") (pinfunction "IO_L7N_3_Y6") (pintype "passive+no_connect"))
    )
    (net (code "159") (name "unconnected-(U10D-IO_L7P_3-PadAA7)") (class "Default")
      (node (ref "U10") (pin "AA7") (pinfunction "IO_L7P_3_AA7") (pintype "passive+no_connect"))
    )
    (net (code "160") (name "unconnected-(U10D-IO_L8N_3-PadAB6)") (class "Default")
      (node (ref "U10") (pin "AB6") (pinfunction "IO_L8N_3_AB6") (pintype "passive+no_connect"))
    )
    (net (code "161") (name "unconnected-(U10D-IO_L8P_3-PadAB7)") (class "Default")
      (node (ref "U10") (pin "AB7") (pinfunction "IO_L8P_3_AB7") (pintype "passive+no_connect"))
    )
    (net (code "162") (name "unconnected-(U10D-IO_L9N_3-PadY8)") (class "Default")
      (node (ref "U10") (pin "Y8") (pinfunction "IO_L9N_3_Y8") (pintype "passive+no_connect"))
    )
    (net (code "163") (name "unconnected-(U10D-IO_L9P_3-PadY9)") (class "Default")
      (node (ref "U10") (pin "Y9") (pinfunction "IO_L9P_3_Y9") (pintype "passive+no_connect"))
    )
    (net (code "164") (name "unconnected-(U10D-IO_L10N_3-PadAD5)") (class "Default")
      (node (ref "U10") (pin "AD5") (pinfunction "IO_L10N_3_AD5") (pintype "passive+no_connect"))
    )
    (net (code "165") (name "unconnected-(U10D-IO_L10P_3-PadAC5)") (class "Default")
      (node (ref "U10") (pin "AC5") (pinfunction "IO_L10P_3_AC5") (pintype "passive+no_connect"))
    )
    (net (code "166") (name "unconnected-(U10D-IO_L15N_3-PadW7)") (class "Default")
      (node (ref "U10") (pin "W7") (pinfunction "IO_L15N_3_W7") (pintype "passive+no_connect"))
    )
    (net (code "167") (name "unconnected-(U10D-IO_L15P_3-PadW8)") (class "Default")
      (node (ref "U10") (pin "W8") (pinfunction "IO_L15P_3_W8") (pintype "passive+no_connect"))
    )
    (net (code "168") (name "unconnected-(U10D-IO_L16N_3-PadAB5)") (class "Default")
      (node (ref "U10") (pin "AB5") (pinfunction "IO_L16N_3_AB5") (pintype "passive+no_connect"))
    )
    (net (code "169") (name "unconnected-(U10D-IO_L16P_3-PadAA5)") (class "Default")
      (node (ref "U10") (pin "AA5") (pinfunction "IO_L16P_3_AA5") (pintype "passive+no_connect"))
    )
    (net (code "170") (name "unconnected-(U10D-IO_L17P_3-PadV7)") (class "Default")
      (node (ref "U10") (pin "V7") (pinfunction "IO_L17P_3_V7") (pintype "passive+no_connect"))
    )
    (net (code "171") (name "unconnected-(U10D-IO_L18N_3-PadAC3)") (class "Default")
      (node (ref "U10") (pin "AC3") (pinfunction "IO_L18N_3_AC3") (pintype "passive+no_connect"))
    )
    (net (code "172") (name "unconnected-(U10D-IO_L18P_3-PadAB4)") (class "Default")
      (node (ref "U10") (pin "AB4") (pinfunction "IO_L18P_3_AB4") (pintype "passive+no_connect"))
    )
    (net (code "173") (name "unconnected-(U10D-IO_L19N_3-PadV8)") (class "Default")
      (node (ref "U10") (pin "V8") (pinfunction "IO_L19N_3_V8") (pintype "passive+no_connect"))
    )
    (net (code "174") (name "unconnected-(U10D-IO_L19P_3-PadW9)") (class "Default")
      (node (ref "U10") (pin "W9") (pinfunction "IO_L19P_3_W9") (pintype "passive+no_connect"))
    )
    (net (code "175") (name "unconnected-(U10D-IO_L20N_3-PadAA3)") (class "Default")
      (node (ref "U10") (pin "AA3") (pinfunction "IO_L20N_3_AA3") (pintype "passive+no_connect"))
    )
    (net (code "176") (name "unconnected-(U10D-IO_L20P_3-PadAA4)") (class "Default")
      (node (ref "U10") (pin "AA4") (pinfunction "IO_L20P_3_AA4") (pintype "passive+no_connect"))
    )
    (net (code "177") (name "unconnected-(U10D-IO_L21N_3-PadV10)") (class "Default")
      (node (ref "U10") (pin "V10") (pinfunction "IO_L21N_3_V10") (pintype "passive+no_connect"))
    )
    (net (code "178") (name "unconnected-(U10D-IO_L21P_3-PadW10)") (class "Default")
      (node (ref "U10") (pin "W10") (pinfunction "IO_L21P_3_W10") (pintype "passive+no_connect"))
    )
    (net (code "179") (name "unconnected-(U10D-IO_L22N_3-PadY5)") (class "Default")
      (node (ref "U10") (pin "Y5") (pinfunction "IO_L22N_3_Y5") (pintype "passive+no_connect"))
    )
    (net (code "180") (name "unconnected-(U10D-IO_L22P_3-PadW5)") (class "Default")
      (node (ref "U10") (pin "W5") (pinfunction "IO_L22P_3_W5") (pintype "passive+no_connect"))
    )
    (net (code "181") (name "unconnected-(U10D-IO_L23N_3-PadU7)") (class "Default")
      (node (ref "U10") (pin "U7") (pinfunction "IO_L23N_3_U7") (pintype "passive+no_connect"))
    )
    (net (code "182") (name "unconnected-(U10D-IO_L23P_3-PadU8)") (class "Default")
      (node (ref "U10") (pin "U8") (pinfunction "IO_L23P_3_U8") (pintype "passive+no_connect"))
    )
    (net (code "183") (name "unconnected-(U10D-IO_L24N_3-PadV5)") (class "Default")
      (node (ref "U10") (pin "V5") (pinfunction "IO_L24N_3_V5") (pintype "passive+no_connect"))
    )
    (net (code "184") (name "unconnected-(U10D-IO_L24P_3-PadU5)") (class "Default")
      (node (ref "U10") (pin "U5") (pinfunction "IO_L24P_3_U5") (pintype "passive+no_connect"))
    )
    (net (code "185") (name "unconnected-(U10D-IO_L25N_3-PadU9)") (class "Default")
      (node (ref "U10") (pin "U9") (pinfunction "IO_L25N_3_U9") (pintype "passive+no_connect"))
    )
    (net (code "186") (name "unconnected-(U10D-IO_L25P_3-PadT10)") (class "Default")
      (node (ref "U10") (pin "T10") (pinfunction "IO_L25P_3_T10") (pintype "passive+no_connect"))
    )
    (net (code "187") (name "unconnected-(U10D-IO_L27N_3-PadT9)") (class "Default")
      (node (ref "U10") (pin "T9") (pinfunction "IO_L27N_3_T9") (pintype "passive+no_connect"))
    )
    (net (code "188") (name "unconnected-(U10D-IO_L27P_3-PadR10)") (class "Default")
      (node (ref "U10") (pin "R10") (pinfunction "IO_L27P_3_R10") (pintype "passive+no_connect"))
    )
    (net (code "189") (name "unconnected-(U10D-IO_L28N_3-PadU3)") (class "Default")
      (node (ref "U10") (pin "U3") (pinfunction "IO_L28N_3_U3") (pintype "passive+no_connect"))
    )
    (net (code "190") (name "unconnected-(U10D-IO_L28P_3-PadU4)") (class "Default")
      (node (ref "U10") (pin "U4") (pinfunction "IO_L28P_3_U4") (pintype "passive+no_connect"))
    )
    (net (code "191") (name "unconnected-(U10D-IO_L29N_3-PadT6)") (class "Default")
      (node (ref "U10") (pin "T6") (pinfunction "IO_L29N_3_T6") (pintype "passive+no_connect"))
    )
    (net (code "192") (name "unconnected-(U10D-IO_L29P_3-PadT8)") (class "Default")
      (node (ref "U10") (pin "T8") (pinfunction "IO_L29P_3_T8") (pintype "passive+no_connect"))
    )
    (net (code "193") (name "unconnected-(U10D-IO_L30N_3-PadT4)") (class "Default")
      (node (ref "U10") (pin "T4") (pinfunction "IO_L30N_3_T4") (pintype "passive+no_connect"))
    )
    (net (code "194") (name "unconnected-(U10D-IO_L30P_3-PadR5)") (class "Default")
      (node (ref "U10") (pin "R5") (pinfunction "IO_L30P_3_R5") (pintype "passive+no_connect"))
    )
    (net (code "195") (name "unconnected-(U10D-IO_L31P_3-PadR7)") (class "Default")
      (node (ref "U10") (pin "R7") (pinfunction "IO_L31P_3_R7") (pintype "passive+no_connect"))
    )
    (net (code "196") (name "unconnected-(U10D-IO_L55N_M3A14_3-PadM4)") (class "Default")
      (node (ref "U10") (pin "M4") (pinfunction "IO_L55N_M3A14_3_M4") (pintype "passive+no_connect"))
    )
    (net (code "197") (name "unconnected-(U10G-RFUSE-PadAA20)") (class "Default")
      (node (ref "U10") (pin "AA20") (pinfunction "RFUSE_AA20") (pintype "passive+no_connect"))
    )
    (net (code "198") (name "unconnected-(U10G-SUSPEND-PadAD23)") (class "Default")
      (node (ref "U10") (pin "AD23") (pinfunction "SUSPEND_AD23") (pintype "passive+no_connect"))
    )
    (net (code "199") (name "unconnected-(U10G-VBATT-PadW21)") (class "Default")
      (node (ref "U10") (pin "W21") (pinfunction "VBATT_W21") (pintype "passive+no_connect"))
    )
    (net (code "200") (name "unconnected-(U10G-VFS-PadAB19)") (class "Default")
      (node (ref "U10") (pin "AB19") (pinfunction "VFS_AB19") (pintype "passive+no_connect"))
    )
  )
)
